# 03_peripheral.net
KiCad netlist of a schematic drawn in Altium Designer
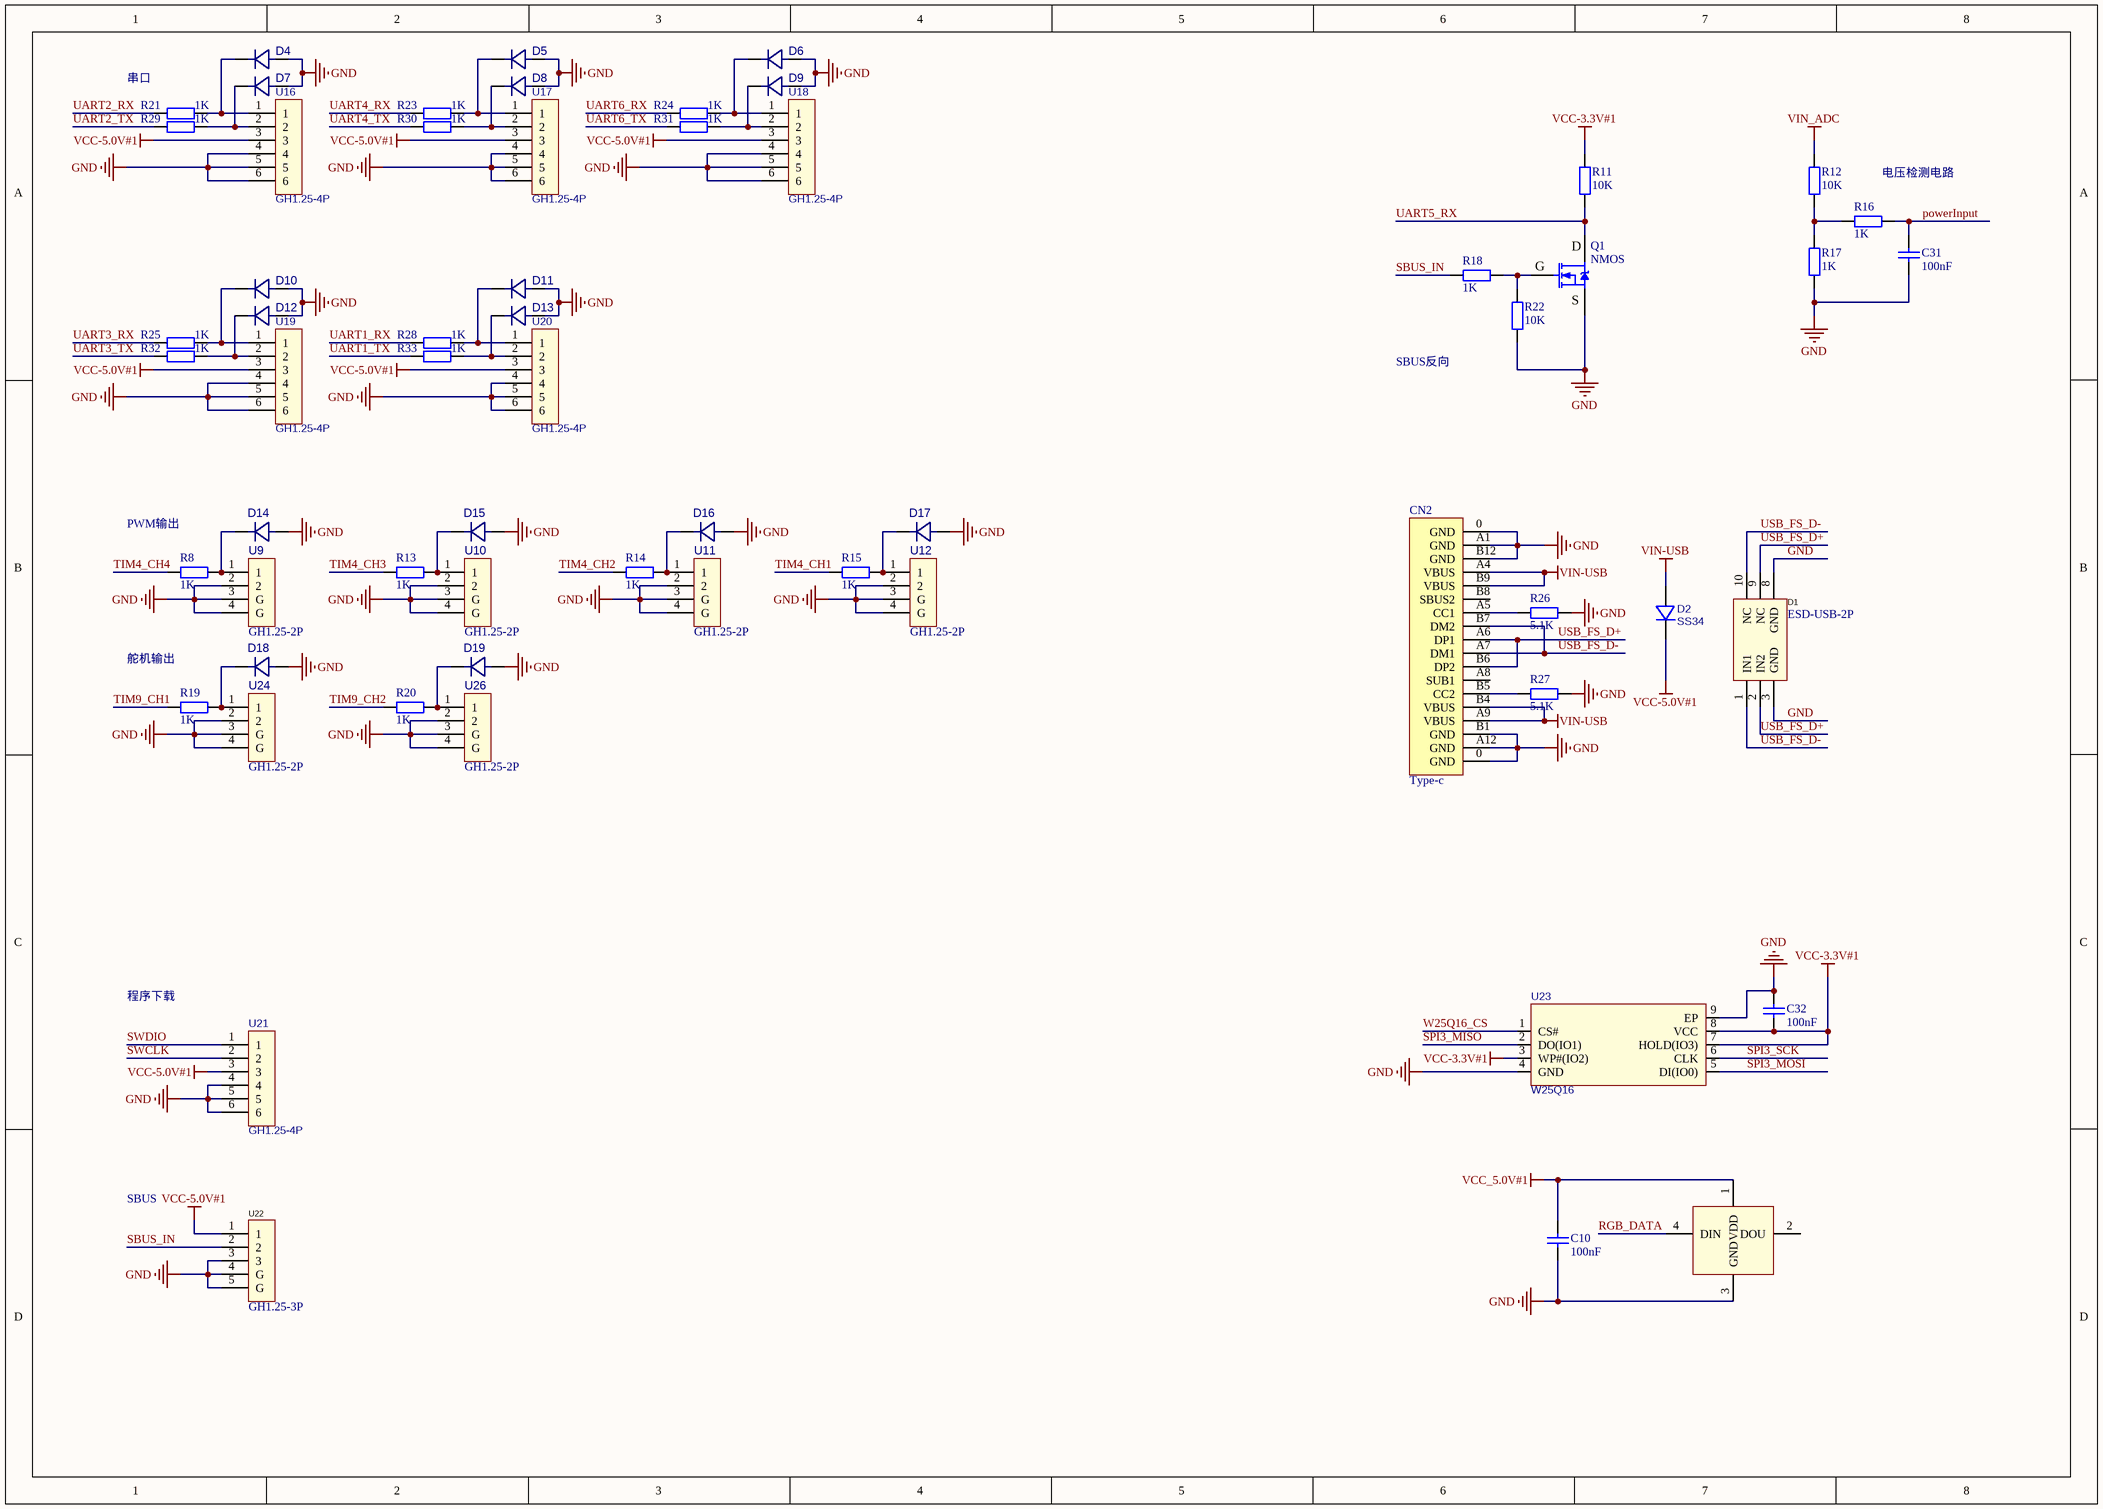
[diagram p0: 03_peripheral.SchDoc]

(export (version "E")
  (design (tool "Eeschema 10.0.6"))
  (components
    (comp (ref "C10")
      (value "100nF")
      (footprint "0603-C")
      (description "贴片电容")
      (libsource (lib "封装库") (part "C"))
    )
    (comp (ref "C31")
      (value "100nF")
      (footprint "0603-C")
      (description "贴片电容")
      (libsource (lib "封装库") (part "C"))
    )
    (comp (ref "C32")
      (value "100nF")
      (footprint "0603-C")
      (description "贴片电容")
      (libsource (lib "封装库") (part "C"))
    )
    (comp (ref "CN2")
      (value "Type-c")
      (footprint "Type-c 16pin")
      (description "U262-161N-4BVC11")
      (libsource (lib "封装库") (part "Type-c"))
    )
    (comp (ref "D1")
      (value "ESD-USB-2P")
      (footprint "SLP2510P8-2P")
      (description "RClamp0522PATCT")
      (fields (field (name "MANUFACTURER") "SEMTECH") (field (name "MANUFACTURER PART") "RClamp0524PATCT"))
      (libsource (lib "封装库") (part "ESD-USB-2P"))
    )
    (comp (ref "D2")
      (value "SS34")
      (footprint "SS34-SMA")
      (fields
        (field (name "BOM_SUPPLIER PART") "C118334")
        (field (name "BOM_MANUFACTURER PART") "D-G060306G1-KS2")
        (field (name "CONTRIBUTOR") "LCSC")
      )
      (libsource (lib "封装库") (part "SS34"))
    )
    (comp (ref "D4")
      (value "ESD9X5.0ST5G")
      (footprint "ESD9X5.0ST5G")
      (fields (field (name "MANUFACTURER") "MSKSEMI(美森科)"))
      (libsource (lib "封装库") (part "ESD9X5.0ST5G"))
    )
    (comp (ref "D5")
      (value "ESD9X5.0ST5G")
      (footprint "ESD9X5.0ST5G")
      (fields (field (name "MANUFACTURER") "MSKSEMI(美森科)"))
      (libsource (lib "封装库") (part "ESD9X5.0ST5G"))
    )
    (comp (ref "D6")
      (value "ESD9X5.0ST5G")
      (footprint "ESD9X5.0ST5G")
      (fields (field (name "MANUFACTURER") "MSKSEMI(美森科)"))
      (libsource (lib "封装库") (part "ESD9X5.0ST5G"))
    )
    (comp (ref "D7")
      (value "ESD9X5.0ST5G")
      (footprint "ESD9X5.0ST5G")
      (fields (field (name "MANUFACTURER") "MSKSEMI(美森科)"))
      (libsource (lib "封装库") (part "ESD9X5.0ST5G"))
    )
    (comp (ref "D8")
      (value "ESD9X5.0ST5G")
      (footprint "ESD9X5.0ST5G")
      (fields (field (name "MANUFACTURER") "MSKSEMI(美森科)"))
      (libsource (lib "封装库") (part "ESD9X5.0ST5G"))
    )
    (comp (ref "D9")
      (value "ESD9X5.0ST5G")
      (footprint "ESD9X5.0ST5G")
      (fields (field (name "MANUFACTURER") "MSKSEMI(美森科)"))
      (libsource (lib "封装库") (part "ESD9X5.0ST5G"))
    )
    (comp (ref "D10")
      (value "ESD9X5.0ST5G")
      (footprint "ESD9X5.0ST5G")
      (fields (field (name "MANUFACTURER") "MSKSEMI(美森科)"))
      (libsource (lib "封装库") (part "ESD9X5.0ST5G"))
    )
    (comp (ref "D11")
      (value "ESD9X5.0ST5G")
      (footprint "ESD9X5.0ST5G")
      (fields (field (name "MANUFACTURER") "MSKSEMI(美森科)"))
      (libsource (lib "封装库") (part "ESD9X5.0ST5G"))
    )
    (comp (ref "D12")
      (value "ESD9X5.0ST5G")
      (footprint "ESD9X5.0ST5G")
      (fields (field (name "MANUFACTURER") "MSKSEMI(美森科)"))
      (libsource (lib "封装库") (part "ESD9X5.0ST5G"))
    )
    (comp (ref "D13")
      (value "ESD9X5.0ST5G")
      (footprint "ESD9X5.0ST5G")
      (fields (field (name "MANUFACTURER") "MSKSEMI(美森科)"))
      (libsource (lib "封装库") (part "ESD9X5.0ST5G"))
    )
    (comp (ref "D14")
      (value "ESD9X5.0ST5G")
      (footprint "ESD9X5.0ST5G")
      (fields (field (name "MANUFACTURER") "MSKSEMI(美森科)"))
      (libsource (lib "封装库") (part "ESD9X5.0ST5G"))
    )
    (comp (ref "D15")
      (value "ESD9X5.0ST5G")
      (footprint "ESD9X5.0ST5G")
      (fields (field (name "MANUFACTURER") "MSKSEMI(美森科)"))
      (libsource (lib "封装库") (part "ESD9X5.0ST5G"))
    )
    (comp (ref "D16")
      (value "ESD9X5.0ST5G")
      (footprint "ESD9X5.0ST5G")
      (fields (field (name "MANUFACTURER") "MSKSEMI(美森科)"))
      (libsource (lib "封装库") (part "ESD9X5.0ST5G"))
    )
    (comp (ref "D17")
      (value "ESD9X5.0ST5G")
      (footprint "ESD9X5.0ST5G")
      (fields (field (name "MANUFACTURER") "MSKSEMI(美森科)"))
      (libsource (lib "封装库") (part "ESD9X5.0ST5G"))
    )
    (comp (ref "D18")
      (value "ESD9X5.0ST5G")
      (footprint "ESD9X5.0ST5G")
      (fields (field (name "MANUFACTURER") "MSKSEMI(美森科)"))
      (libsource (lib "封装库") (part "ESD9X5.0ST5G"))
    )
    (comp (ref "D19")
      (value "ESD9X5.0ST5G")
      (footprint "ESD9X5.0ST5G")
      (fields (field (name "MANUFACTURER") "MSKSEMI(美森科)"))
      (libsource (lib "封装库") (part "ESD9X5.0ST5G"))
    )
    (comp (ref "LED3")
      (value "WS2812B-5050")
      (footprint "WS2812B-5050")
      (fields
        (field (name "MANUFACTURER") "XINGLIGHT(成兴光)")
        (field (name "MANUFACTURER PART") "XL-5050RGBC-WS2812B")
      )
      (libsource (lib "封装库") (part "WS2812B-5050"))
    )
    (comp (ref "Q1")
      (value "NMOS")
      (footprint "SOT23-3M")
      (description "N沟道 30V/4.2A")
      (libsource (lib "封装库") (part "AO3400"))
    )
    (comp (ref "R8")
      (value "1K")
      (footprint "0603-R")
      (description "贴片电阻")
      (libsource (lib "封装库") (part "R"))
    )
    (comp (ref "R11")
      (value "10K")
      (footprint "0603-R")
      (description "贴片电阻")
      (libsource (lib "封装库") (part "R"))
    )
    (comp (ref "R12")
      (value "10K")
      (footprint "0603-R")
      (description "贴片电阻")
      (libsource (lib "封装库") (part "R"))
    )
    (comp (ref "R13")
      (value "1K")
      (footprint "0603-R")
      (description "贴片电阻")
      (libsource (lib "封装库") (part "R"))
    )
    (comp (ref "R14")
      (value "1K")
      (footprint "0603-R")
      (description "贴片电阻")
      (libsource (lib "封装库") (part "R"))
    )
    (comp (ref "R15")
      (value "1K")
      (footprint "0603-R")
      (description "贴片电阻")
      (libsource (lib "封装库") (part "R"))
    )
    (comp (ref "R16")
      (value "1K")
      (footprint "0603-R")
      (description "贴片电阻")
      (libsource (lib "封装库") (part "R"))
    )
    (comp (ref "R17")
      (value "1K")
      (footprint "0603-R")
      (description "贴片电阻")
      (libsource (lib "封装库") (part "R"))
    )
    (comp (ref "R18")
      (value "1K")
      (footprint "0603-R")
      (description "贴片电阻")
      (libsource (lib "封装库") (part "R"))
    )
    (comp (ref "R19")
      (value "1K")
      (footprint "0603-R")
      (description "贴片电阻")
      (libsource (lib "封装库") (part "R"))
    )
    (comp (ref "R20")
      (value "1K")
      (footprint "0603-R")
      (description "贴片电阻")
      (libsource (lib "封装库") (part "R"))
    )
    (comp (ref "R21")
      (value "1K")
      (footprint "0603-R")
      (description "贴片电阻")
      (libsource (lib "封装库") (part "R"))
    )
    (comp (ref "R22")
      (value "10K")
      (footprint "0603-R")
      (description "贴片电阻")
      (libsource (lib "封装库") (part "R"))
    )
    (comp (ref "R23")
      (value "1K")
      (footprint "0603-R")
      (description "贴片电阻")
      (libsource (lib "封装库") (part "R"))
    )
    (comp (ref "R24")
      (value "1K")
      (footprint "0603-R")
      (description "贴片电阻")
      (libsource (lib "封装库") (part "R"))
    )
    (comp (ref "R25")
      (value "1K")
      (footprint "0603-R")
      (description "贴片电阻")
      (libsource (lib "封装库") (part "R"))
    )
    (comp (ref "R26")
      (value "5.1K")
      (footprint "0603-R")
      (description "贴片电阻")
      (libsource (lib "封装库") (part "R"))
    )
    (comp (ref "R27")
      (value "5.1K")
      (footprint "0603-R")
      (description "贴片电阻")
      (libsource (lib "封装库") (part "R"))
    )
    (comp (ref "R28")
      (value "1K")
      (footprint "0603-R")
      (description "贴片电阻")
      (libsource (lib "封装库") (part "R"))
    )
    (comp (ref "R29")
      (value "1K")
      (footprint "0603-R")
      (description "贴片电阻")
      (libsource (lib "封装库") (part "R"))
    )
    (comp (ref "R30")
      (value "1K")
      (footprint "0603-R")
      (description "贴片电阻")
      (libsource (lib "封装库") (part "R"))
    )
    (comp (ref "R31")
      (value "1K")
      (footprint "0603-R")
      (description "贴片电阻")
      (libsource (lib "封装库") (part "R"))
    )
    (comp (ref "R32")
      (value "1K")
      (footprint "0603-R")
      (description "贴片电阻")
      (libsource (lib "封装库") (part "R"))
    )
    (comp (ref "R33")
      (value "1K")
      (footprint "0603-R")
      (description "贴片电阻")
      (libsource (lib "封装库") (part "R"))
    )
    (comp (ref "U9")
      (value "GH1.25-2P")
      (footprint "GH1.25-2P")
      (fields (field (name "MANUFACTURER") "Bossie(博锡)") (field (name "MANUFACTURER PART") "BX-GH1.25-2PWT"))
      (libsource (lib "封装库") (part "GH1.25-2P"))
    )
    (comp (ref "U10")
      (value "GH1.25-2P")
      (footprint "GH1.25-2P")
      (fields (field (name "MANUFACTURER") "Bossie(博锡)") (field (name "MANUFACTURER PART") "BX-GH1.25-2PWT"))
      (libsource (lib "封装库") (part "GH1.25-2P"))
    )
    (comp (ref "U11")
      (value "GH1.25-2P")
      (footprint "GH1.25-2P")
      (fields (field (name "MANUFACTURER") "Bossie(博锡)") (field (name "MANUFACTURER PART") "BX-GH1.25-2PWT"))
      (libsource (lib "封装库") (part "GH1.25-2P"))
    )
    (comp (ref "U12")
      (value "GH1.25-2P")
      (footprint "GH1.25-2P")
      (fields (field (name "MANUFACTURER") "Bossie(博锡)") (field (name "MANUFACTURER PART") "BX-GH1.25-2PWT"))
      (libsource (lib "封装库") (part "GH1.25-2P"))
    )
    (comp (ref "U16")
      (value "GH1.25-4P")
      (footprint "CONN-SMD_GH1.25-4PWBPZ")
      (description "GH1.25-4PWBPZ")
      (fields (field (name "BOM_SUPPLIER PART") "C2829253") (field (name "CONTRIBUTOR") "LCSC"))
      (libsource (lib "封装库") (part "GH1.25-4P"))
    )
    (comp (ref "U17")
      (value "GH1.25-4P")
      (footprint "CONN-SMD_GH1.25-4PWBPZ")
      (description "GH1.25-4PWBPZ")
      (fields (field (name "BOM_SUPPLIER PART") "C2829253") (field (name "CONTRIBUTOR") "LCSC"))
      (libsource (lib "封装库") (part "GH1.25-4P"))
    )
    (comp (ref "U18")
      (value "GH1.25-4P")
      (footprint "CONN-SMD_GH1.25-4PWBPZ")
      (description "GH1.25-4PWBPZ")
      (fields (field (name "BOM_SUPPLIER PART") "C2829253") (field (name "CONTRIBUTOR") "LCSC"))
      (libsource (lib "封装库") (part "GH1.25-4P"))
    )
    (comp (ref "U19")
      (value "GH1.25-4P")
      (footprint "CONN-SMD_GH1.25-4PWBPZ")
      (description "GH1.25-4PWBPZ")
      (fields (field (name "BOM_SUPPLIER PART") "C2829253") (field (name "CONTRIBUTOR") "LCSC"))
      (libsource (lib "封装库") (part "GH1.25-4P"))
    )
    (comp (ref "U20")
      (value "GH1.25-4P")
      (footprint "CONN-SMD_GH1.25-4PWBPZ")
      (description "GH1.25-4PWBPZ")
      (fields (field (name "BOM_SUPPLIER PART") "C2829253") (field (name "CONTRIBUTOR") "LCSC"))
      (libsource (lib "封装库") (part "GH1.25-4P"))
    )
    (comp (ref "U21")
      (value "GH1.25-4P")
      (footprint "CONN-SMD_GH1.25-4PWBPZ")
      (description "GH1.25-4PWBPZ")
      (fields (field (name "BOM_SUPPLIER PART") "C2829253") (field (name "CONTRIBUTOR") "LCSC"))
      (libsource (lib "封装库") (part "GH1.25-4P"))
    )
    (comp (ref "U22")
      (value "GH1.25-3P")
      (footprint "GH1.25-3P")
      (fields (field (name "MANUFACTURER") "Bossie(博锡)") (field (name "MANUFACTURER PART") "BX-GH1.25-3PWT"))
      (libsource (lib "封装库") (part "GH1.25-3P"))
    )
    (comp (ref "U23")
      (value "W25Q16")
      (footprint "W25QXX_WSON_8_5*6mm")
      (fields
        (field (name "BOM_SUPPLIER PART") "C2682312")
        (field (name "BOM_MANUFACTURER PART") "W25Q256JVEIQ")
        (field (name "CONTRIBUTOR") "LCSC")
      )
      (libsource (lib "封装库") (part "W25Q256"))
    )
    (comp (ref "U24")
      (value "GH1.25-2P")
      (footprint "GH1.25-2P")
      (fields (field (name "MANUFACTURER") "Bossie(博锡)") (field (name "MANUFACTURER PART") "BX-GH1.25-2PWT"))
      (libsource (lib "封装库") (part "GH1.25-2P"))
    )
    (comp (ref "U26")
      (value "GH1.25-2P")
      (footprint "GH1.25-2P")
      (fields (field (name "MANUFACTURER") "Bossie(博锡)") (field (name "MANUFACTURER PART") "BX-GH1.25-2PWT"))
      (libsource (lib "封装库") (part "GH1.25-2P"))
    )
  )
  (nets
    (net (code "1") (name "/RGB_DATA") (class "Default")
      (node (ref "LED3") (pin "4") (pinfunction "DIN_4") (pintype "passive"))
    )
    (net (code "2") (name "/SBUS_IN") (class "Default")
      (node (ref "R18") (pin "1") (pinfunction "1_1") (pintype "passive"))
      (node (ref "U22") (pin "2") (pinfunction "2_2") (pintype "passive"))
    )
    (net (code "3") (name "/SPI3_MISO") (class "Default")
      (node (ref "U23") (pin "2") (pinfunction "DO(IO1)_2") (pintype "passive"))
    )
    (net (code "4") (name "/SPI3_MOSI") (class "Default")
      (node (ref "U23") (pin "5") (pinfunction "DI(IO0)_5") (pintype "passive"))
    )
    (net (code "5") (name "/SPI3_SCK") (class "Default")
      (node (ref "U23") (pin "6") (pinfunction "CLK_6") (pintype "passive"))
    )
    (net (code "6") (name "/SWCLK") (class "Default")
      (node (ref "U21") (pin "2") (pinfunction "2_2") (pintype "passive"))
    )
    (net (code "7") (name "/SWDIO") (class "Default")
      (node (ref "U21") (pin "1") (pinfunction "1_1") (pintype "passive"))
    )
    (net (code "8") (name "/TIM4_CH1") (class "Default")
      (node (ref "R15") (pin "1") (pinfunction "1_1") (pintype "passive"))
    )
    (net (code "9") (name "/TIM4_CH2") (class "Default")
      (node (ref "R14") (pin "1") (pinfunction "1_1") (pintype "passive"))
    )
    (net (code "10") (name "/TIM4_CH3") (class "Default")
      (node (ref "R13") (pin "1") (pinfunction "1_1") (pintype "passive"))
    )
    (net (code "11") (name "/TIM4_CH4") (class "Default")
      (node (ref "R8") (pin "1") (pinfunction "1_1") (pintype "passive"))
    )
    (net (code "12") (name "/TIM9_CH1") (class "Default")
      (node (ref "R19") (pin "1") (pinfunction "1_1") (pintype "passive"))
    )
    (net (code "13") (name "/TIM9_CH2") (class "Default")
      (node (ref "R20") (pin "1") (pinfunction "1_1") (pintype "passive"))
    )
    (net (code "14") (name "/UART1_RX") (class "Default")
      (node (ref "R28") (pin "1") (pinfunction "1_1") (pintype "passive"))
    )
    (net (code "15") (name "/UART1_TX") (class "Default")
      (node (ref "R33") (pin "1") (pinfunction "1_1") (pintype "passive"))
    )
    (net (code "16") (name "/UART2_RX") (class "Default")
      (node (ref "R21") (pin "1") (pinfunction "1_1") (pintype "passive"))
    )
    (net (code "17") (name "/UART2_TX") (class "Default")
      (node (ref "R29") (pin "1") (pinfunction "1_1") (pintype "passive"))
    )
    (net (code "18") (name "/UART3_RX") (class "Default")
      (node (ref "R25") (pin "1") (pinfunction "1_1") (pintype "passive"))
    )
    (net (code "19") (name "/UART3_TX") (class "Default")
      (node (ref "R32") (pin "1") (pinfunction "1_1") (pintype "passive"))
    )
    (net (code "20") (name "/UART4_RX") (class "Default")
      (node (ref "R23") (pin "1") (pinfunction "1_1") (pintype "passive"))
    )
    (net (code "21") (name "/UART4_TX") (class "Default")
      (node (ref "R30") (pin "1") (pinfunction "1_1") (pintype "passive"))
    )
    (net (code "22") (name "/UART5_RX") (class "Default")
      (node (ref "Q1") (pin "3") (pinfunction "D_3") (pintype "passive"))
      (node (ref "R11") (pin "1") (pinfunction "1_1") (pintype "passive"))
    )
    (net (code "23") (name "/UART6_RX") (class "Default")
      (node (ref "R24") (pin "1") (pinfunction "1_1") (pintype "passive"))
    )
    (net (code "24") (name "/UART6_TX") (class "Default")
      (node (ref "R31") (pin "1") (pinfunction "1_1") (pintype "passive"))
    )
    (net (code "25") (name "/USB_FS_D+") (class "Default")
      (node (ref "CN2") (pin "A6") (pinfunction "DP1_A6") (pintype "passive"))
      (node (ref "CN2") (pin "B6") (pinfunction "DP2_B6") (pintype "passive"))
      (node (ref "D1") (pin "2") (pinfunction "IN2_2") (pintype "passive"))
      (node (ref "D1") (pin "9") (pinfunction "NC_9") (pintype "passive"))
    )
    (net (code "26") (name "/USB_FS_D-") (class "Default")
      (node (ref "CN2") (pin "A7") (pinfunction "DM1_A7") (pintype "passive"))
      (node (ref "CN2") (pin "B7") (pinfunction "DM2_B7") (pintype "passive"))
      (node (ref "D1") (pin "1") (pinfunction "IN1_1") (pintype "passive"))
      (node (ref "D1") (pin "10") (pinfunction "NC_10") (pintype "passive"))
    )
    (net (code "27") (name "/W25Q16_CS") (class "Default")
      (node (ref "U23") (pin "1") (pinfunction "CS#_1") (pintype "passive"))
    )
    (net (code "28") (name "/powerInput") (class "Default")
      (node (ref "C31") (pin "2") (pinfunction "2_2") (pintype "passive"))
      (node (ref "R16") (pin "2") (pinfunction "2_2") (pintype "passive"))
    )
    (net (code "29") (name "GND") (class "Default")
      (node (ref "C10") (pin "1") (pinfunction "1_1") (pintype "passive"))
      (node (ref "C31") (pin "1") (pinfunction "1_1") (pintype "passive"))
      (node (ref "C32") (pin "2") (pinfunction "2_2") (pintype "passive"))
      (node (ref "CN2") (pin "0") (pinfunction "GND_0") (pintype "passive"))
      (node (ref "CN2") (pin "A1") (pinfunction "GND_A1") (pintype "passive"))
      (node (ref "CN2") (pin "A12") (pinfunction "GND_A12") (pintype "passive"))
      (node (ref "CN2") (pin "B1") (pinfunction "GND_B1") (pintype "passive"))
      (node (ref "CN2") (pin "B12") (pinfunction "GND_B12") (pintype "passive"))
      (node (ref "D1") (pin "3") (pinfunction "GND_3") (pintype "passive"))
      (node (ref "D1") (pin "8") (pinfunction "GND_8") (pintype "passive"))
      (node (ref "D10") (pin "2") (pinfunction "A_2") (pintype "passive"))
      (node (ref "D11") (pin "2") (pinfunction "A_2") (pintype "passive"))
      (node (ref "D12") (pin "2") (pinfunction "A_2") (pintype "passive"))
      (node (ref "D13") (pin "2") (pinfunction "A_2") (pintype "passive"))
      (node (ref "D14") (pin "2") (pinfunction "A_2") (pintype "passive"))
      (node (ref "D15") (pin "2") (pinfunction "A_2") (pintype "passive"))
      (node (ref "D16") (pin "2") (pinfunction "A_2") (pintype "passive"))
      (node (ref "D17") (pin "2") (pinfunction "A_2") (pintype "passive"))
      (node (ref "D18") (pin "2") (pinfunction "A_2") (pintype "passive"))
      (node (ref "D19") (pin "2") (pinfunction "A_2") (pintype "passive"))
      (node (ref "D4") (pin "2") (pinfunction "A_2") (pintype "passive"))
      (node (ref "D5") (pin "2") (pinfunction "A_2") (pintype "passive"))
      (node (ref "D6") (pin "2") (pinfunction "A_2") (pintype "passive"))
      (node (ref "D7") (pin "2") (pinfunction "A_2") (pintype "passive"))
      (node (ref "D8") (pin "2") (pinfunction "A_2") (pintype "passive"))
      (node (ref "D9") (pin "2") (pinfunction "A_2") (pintype "passive"))
      (node (ref "LED3") (pin "3") (pinfunction "GND_3") (pintype "passive"))
      (node (ref "Q1") (pin "2") (pinfunction "S_2") (pintype "passive"))
      (node (ref "R17") (pin "1") (pinfunction "1_1") (pintype "passive"))
      (node (ref "R22") (pin "1") (pinfunction "1_1") (pintype "passive"))
      (node (ref "R26") (pin "2") (pinfunction "2_2") (pintype "passive"))
      (node (ref "R27") (pin "2") (pinfunction "2_2") (pintype "passive"))
      (node (ref "U10") (pin "2") (pinfunction "2_2") (pintype "passive"))
      (node (ref "U10") (pin "3") (pinfunction "G_3") (pintype "passive"))
      (node (ref "U10") (pin "4") (pinfunction "G_4") (pintype "passive"))
      (node (ref "U11") (pin "2") (pinfunction "2_2") (pintype "passive"))
      (node (ref "U11") (pin "3") (pinfunction "G_3") (pintype "passive"))
      (node (ref "U11") (pin "4") (pinfunction "G_4") (pintype "passive"))
      (node (ref "U12") (pin "2") (pinfunction "2_2") (pintype "passive"))
      (node (ref "U12") (pin "3") (pinfunction "G_3") (pintype "passive"))
      (node (ref "U12") (pin "4") (pinfunction "G_4") (pintype "passive"))
      (node (ref "U16") (pin "4") (pinfunction "4_4") (pintype "passive"))
      (node (ref "U16") (pin "5") (pinfunction "5_5") (pintype "passive"))
      (node (ref "U16") (pin "6") (pinfunction "6_6") (pintype "passive"))
      (node (ref "U17") (pin "4") (pinfunction "4_4") (pintype "passive"))
      (node (ref "U17") (pin "5") (pinfunction "5_5") (pintype "passive"))
      (node (ref "U17") (pin "6") (pinfunction "6_6") (pintype "passive"))
      (node (ref "U18") (pin "4") (pinfunction "4_4") (pintype "passive"))
      (node (ref "U18") (pin "5") (pinfunction "5_5") (pintype "passive"))
      (node (ref "U18") (pin "6") (pinfunction "6_6") (pintype "passive"))
      (node (ref "U19") (pin "4") (pinfunction "4_4") (pintype "passive"))
      (node (ref "U19") (pin "5") (pinfunction "5_5") (pintype "passive"))
      (node (ref "U19") (pin "6") (pinfunction "6_6") (pintype "passive"))
      (node (ref "U20") (pin "4") (pinfunction "4_4") (pintype "passive"))
      (node (ref "U20") (pin "5") (pinfunction "5_5") (pintype "passive"))
      (node (ref "U20") (pin "6") (pinfunction "6_6") (pintype "passive"))
      (node (ref "U21") (pin "4") (pinfunction "4_4") (pintype "passive"))
      (node (ref "U21") (pin "5") (pinfunction "5_5") (pintype "passive"))
      (node (ref "U21") (pin "6") (pinfunction "6_6") (pintype "passive"))
      (node (ref "U22") (pin "3") (pinfunction "3_3") (pintype "passive"))
      (node (ref "U22") (pin "4") (pinfunction "G_4") (pintype "passive"))
      (node (ref "U22") (pin "5") (pinfunction "G_5") (pintype "passive"))
      (node (ref "U23") (pin "4") (pinfunction "GND_4") (pintype "passive"))
      (node (ref "U23") (pin "9") (pinfunction "EP_9") (pintype "passive"))
      (node (ref "U24") (pin "2") (pinfunction "2_2") (pintype "passive"))
      (node (ref "U24") (pin "3") (pinfunction "G_3") (pintype "passive"))
      (node (ref "U24") (pin "4") (pinfunction "G_4") (pintype "passive"))
      (node (ref "U26") (pin "2") (pinfunction "2_2") (pintype "passive"))
      (node (ref "U26") (pin "3") (pinfunction "G_3") (pintype "passive"))
      (node (ref "U26") (pin "4") (pinfunction "G_4") (pintype "passive"))
      (node (ref "U9") (pin "2") (pinfunction "2_2") (pintype "passive"))
      (node (ref "U9") (pin "3") (pinfunction "G_3") (pintype "passive"))
      (node (ref "U9") (pin "4") (pinfunction "G_4") (pintype "passive"))
    )
    (net (code "30") (name "Net-(CN2-CC1)") (class "Default")
      (node (ref "CN2") (pin "A5") (pinfunction "CC1_A5") (pintype "passive"))
      (node (ref "R26") (pin "1") (pinfunction "1_1") (pintype "passive"))
    )
    (net (code "31") (name "Net-(CN2-CC2)") (class "Default")
      (node (ref "CN2") (pin "B5") (pinfunction "CC2_B5") (pintype "passive"))
      (node (ref "R27") (pin "1") (pinfunction "1_1") (pintype "passive"))
    )
    (net (code "32") (name "Net-(D4-K)") (class "Default")
      (node (ref "D4") (pin "1") (pinfunction "K_1") (pintype "passive"))
      (node (ref "R21") (pin "2") (pinfunction "2_2") (pintype "passive"))
      (node (ref "U16") (pin "1") (pinfunction "1_1") (pintype "passive"))
    )
    (net (code "33") (name "Net-(D5-K)") (class "Default")
      (node (ref "D5") (pin "1") (pinfunction "K_1") (pintype "passive"))
      (node (ref "R23") (pin "2") (pinfunction "2_2") (pintype "passive"))
      (node (ref "U17") (pin "1") (pinfunction "1_1") (pintype "passive"))
    )
    (net (code "34") (name "Net-(D6-K)") (class "Default")
      (node (ref "D6") (pin "1") (pinfunction "K_1") (pintype "passive"))
      (node (ref "R24") (pin "2") (pinfunction "2_2") (pintype "passive"))
      (node (ref "U18") (pin "1") (pinfunction "1_1") (pintype "passive"))
    )
    (net (code "35") (name "Net-(D7-K)") (class "Default")
      (node (ref "D7") (pin "1") (pinfunction "K_1") (pintype "passive"))
      (node (ref "R29") (pin "2") (pinfunction "2_2") (pintype "passive"))
      (node (ref "U16") (pin "2") (pinfunction "2_2") (pintype "passive"))
    )
    (net (code "36") (name "Net-(D8-K)") (class "Default")
      (node (ref "D8") (pin "1") (pinfunction "K_1") (pintype "passive"))
      (node (ref "R30") (pin "2") (pinfunction "2_2") (pintype "passive"))
      (node (ref "U17") (pin "2") (pinfunction "2_2") (pintype "passive"))
    )
    (net (code "37") (name "Net-(D9-K)") (class "Default")
      (node (ref "D9") (pin "1") (pinfunction "K_1") (pintype "passive"))
      (node (ref "R31") (pin "2") (pinfunction "2_2") (pintype "passive"))
      (node (ref "U18") (pin "2") (pinfunction "2_2") (pintype "passive"))
    )
    (net (code "38") (name "Net-(D10-K)") (class "Default")
      (node (ref "D10") (pin "1") (pinfunction "K_1") (pintype "passive"))
      (node (ref "R25") (pin "2") (pinfunction "2_2") (pintype "passive"))
      (node (ref "U19") (pin "1") (pinfunction "1_1") (pintype "passive"))
    )
    (net (code "39") (name "Net-(D11-K)") (class "Default")
      (node (ref "D11") (pin "1") (pinfunction "K_1") (pintype "passive"))
      (node (ref "R28") (pin "2") (pinfunction "2_2") (pintype "passive"))
      (node (ref "U20") (pin "1") (pinfunction "1_1") (pintype "passive"))
    )
    (net (code "40") (name "Net-(D12-K)") (class "Default")
      (node (ref "D12") (pin "1") (pinfunction "K_1") (pintype "passive"))
      (node (ref "R32") (pin "2") (pinfunction "2_2") (pintype "passive"))
      (node (ref "U19") (pin "2") (pinfunction "2_2") (pintype "passive"))
    )
    (net (code "41") (name "Net-(D13-K)") (class "Default")
      (node (ref "D13") (pin "1") (pinfunction "K_1") (pintype "passive"))
      (node (ref "R33") (pin "2") (pinfunction "2_2") (pintype "passive"))
      (node (ref "U20") (pin "2") (pinfunction "2_2") (pintype "passive"))
    )
    (net (code "42") (name "Net-(D14-K)") (class "Default")
      (node (ref "D14") (pin "1") (pinfunction "K_1") (pintype "passive"))
      (node (ref "R8") (pin "2") (pinfunction "2_2") (pintype "passive"))
      (node (ref "U9") (pin "1") (pinfunction "1_1") (pintype "passive"))
    )
    (net (code "43") (name "Net-(D15-K)") (class "Default")
      (node (ref "D15") (pin "1") (pinfunction "K_1") (pintype "passive"))
      (node (ref "R13") (pin "2") (pinfunction "2_2") (pintype "passive"))
      (node (ref "U10") (pin "1") (pinfunction "1_1") (pintype "passive"))
    )
    (net (code "44") (name "Net-(D16-K)") (class "Default")
      (node (ref "D16") (pin "1") (pinfunction "K_1") (pintype "passive"))
      (node (ref "R14") (pin "2") (pinfunction "2_2") (pintype "passive"))
      (node (ref "U11") (pin "1") (pinfunction "1_1") (pintype "passive"))
    )
    (net (code "45") (name "Net-(D17-K)") (class "Default")
      (node (ref "D17") (pin "1") (pinfunction "K_1") (pintype "passive"))
      (node (ref "R15") (pin "2") (pinfunction "2_2") (pintype "passive"))
      (node (ref "U12") (pin "1") (pinfunction "1_1") (pintype "passive"))
    )
    (net (code "46") (name "Net-(D18-K)") (class "Default")
      (node (ref "D18") (pin "1") (pinfunction "K_1") (pintype "passive"))
      (node (ref "R19") (pin "2") (pinfunction "2_2") (pintype "passive"))
      (node (ref "U24") (pin "1") (pinfunction "1_1") (pintype "passive"))
    )
    (net (code "47") (name "Net-(D19-K)") (class "Default")
      (node (ref "D19") (pin "1") (pinfunction "K_1") (pintype "passive"))
      (node (ref "R20") (pin "2") (pinfunction "2_2") (pintype "passive"))
      (node (ref "U26") (pin "1") (pinfunction "1_1") (pintype "passive"))
    )
    (net (code "48") (name "Net-(Q1-G)") (class "Default")
      (node (ref "Q1") (pin "1") (pinfunction "G_1") (pintype "passive"))
      (node (ref "R18") (pin "2") (pinfunction "2_2") (pintype "passive"))
      (node (ref "R22") (pin "2") (pinfunction "2_2") (pintype "passive"))
    )
    (net (code "49") (name "Net-(R12-Pad1)") (class "Default")
      (node (ref "R12") (pin "1") (pinfunction "1_1") (pintype "passive"))
      (node (ref "R16") (pin "1") (pinfunction "1_1") (pintype "passive"))
      (node (ref "R17") (pin "2") (pinfunction "2_2") (pintype "passive"))
    )
    (net (code "50") (name "VCC-3.3V#1") (class "Default")
      (node (ref "C32") (pin "1") (pinfunction "1_1") (pintype "passive"))
      (node (ref "R11") (pin "2") (pinfunction "2_2") (pintype "passive"))
      (node (ref "U23") (pin "3") (pinfunction "WP#(IO2)_3") (pintype "passive"))
      (node (ref "U23") (pin "7") (pinfunction "HOLD(IO3)_7") (pintype "passive"))
      (node (ref "U23") (pin "8") (pinfunction "VCC_8") (pintype "passive"))
    )
    (net (code "51") (name "VCC-5.0V#1") (class "Default")
      (node (ref "D2") (pin "2") (pinfunction "-_2") (pintype "passive"))
      (node (ref "U16") (pin "3") (pinfunction "3_3") (pintype "passive"))
      (node (ref "U17") (pin "3") (pinfunction "3_3") (pintype "passive"))
      (node (ref "U18") (pin "3") (pinfunction "3_3") (pintype "passive"))
      (node (ref "U19") (pin "3") (pinfunction "3_3") (pintype "passive"))
      (node (ref "U20") (pin "3") (pinfunction "3_3") (pintype "passive"))
      (node (ref "U21") (pin "3") (pinfunction "3_3") (pintype "passive"))
      (node (ref "U22") (pin "1") (pinfunction "1_1") (pintype "passive"))
    )
    (net (code "52") (name "VCC_5.0V#1") (class "Default")
      (node (ref "C10") (pin "2") (pinfunction "2_2") (pintype "passive"))
      (node (ref "LED3") (pin "1") (pinfunction "VDD_1") (pintype "passive"))
    )
    (net (code "53") (name "VIN-USB") (class "Default")
      (node (ref "CN2") (pin "A4") (pinfunction "VBUS_A4") (pintype "passive"))
      (node (ref "CN2") (pin "A9") (pinfunction "VBUS_A9") (pintype "passive"))
      (node (ref "CN2") (pin "B4") (pinfunction "VBUS_B4") (pintype "passive"))
      (node (ref "CN2") (pin "B9") (pinfunction "VBUS_B9") (pintype "passive"))
      (node (ref "D2") (pin "1") (pinfunction "+_1") (pintype "passive"))
    )
    (net (code "54") (name "VIN_ADC") (class "Default")
      (node (ref "R12") (pin "2") (pinfunction "2_2") (pintype "passive"))
    )
    (net (code "55") (name "unconnected-(CN2-SBUS2-PadB8)") (class "Default")
      (node (ref "CN2") (pin "B8") (pinfunction "SBUS2_B8") (pintype "passive"))
    )
    (net (code "56") (name "unconnected-(CN2-SUB1-PadA8)") (class "Default")
      (node (ref "CN2") (pin "A8") (pinfunction "SUB1_A8") (pintype "passive"))
    )
    (net (code "57") (name "unconnected-(LED3-DOU-Pad2)") (class "Default")
      (node (ref "LED3") (pin "2") (pinfunction "DOU_2") (pintype "passive"))
    )
  )
)
